# CON1.net
KiCad netlist of a schematic drawn in Altium Designer
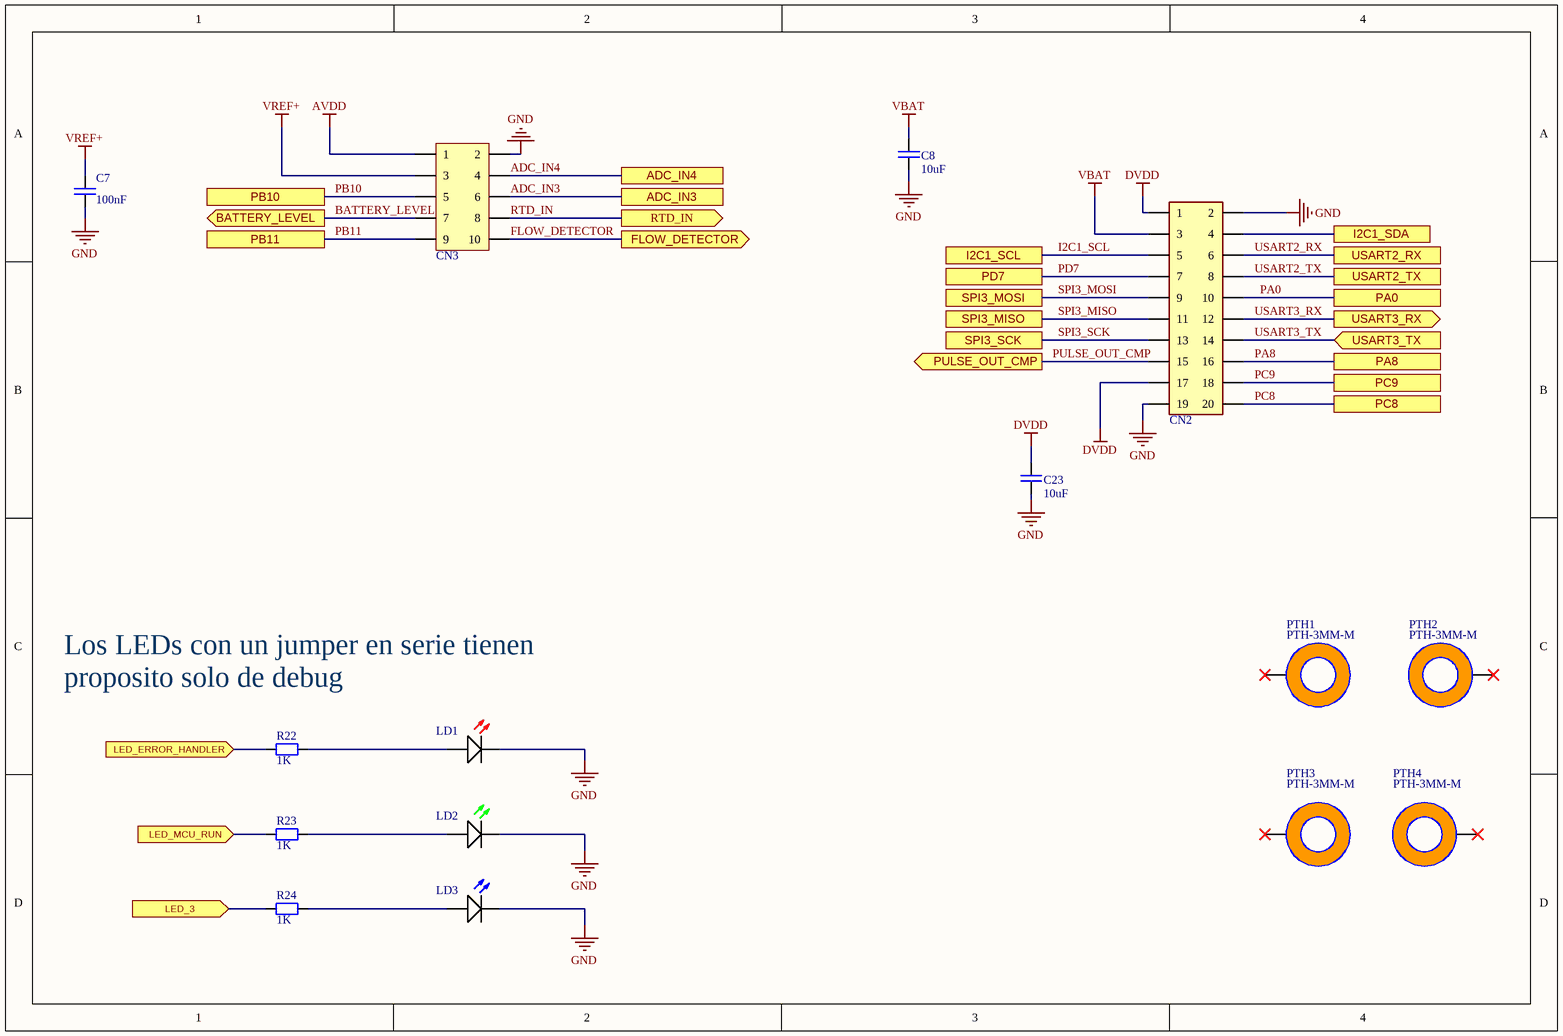
[diagram p0: CON1.SchDoc]

(export (version "E")
  (design (tool "Eeschema 10.0.6"))
  (components
    (comp (ref "C7")
      (value "100nF")
      (footprint "CAP_SM0805_YAGEOCC2_N")
      (description "CAP 100nF SM0805 X7R 50V YAGEO CC2")
      (fields
        (field (name "MANUFACTURER") "Yageo")
        (field (name "MANUFACTURER PART NUMBER") "CC0805KRX7R9BB104")
      )
      (libsource (lib "Yageo") (part "CC0805KRX7R9BB104"))
    )
    (comp (ref "C8")
      (value "10uF")
      (footprint "CAP_SM0805_YAGEOCC2_N")
      (description "CAP 10uF SM0805 X5R 25V YAGEO")
      (fields
        (field (name "MANUFACTURER") "Yageo")
        (field (name "MANUFACTURER PART NUMBER") "CC0805KKX5R8BB106")
      )
      (libsource (lib "Yageo") (part "CC0805KKX5R8BB106"))
    )
    (comp (ref "C23")
      (value "10uF")
      (footprint "CAP_SM0805_YAGEOCC2_N")
      (description "CAP 10uF SM0805 X5R 25V YAGEO")
      (fields
        (field (name "MANUFACTURER") "Yageo")
        (field (name "MANUFACTURER PART NUMBER") "CC0805KKX5R8BB106")
      )
      (libsource (lib "Yageo") (part "CC0805KKX5R8BB106"))
    )
    (comp (ref "CN2")
      (value "DW254R-22-20-85")
      (footprint "DW254R-22-10-85")
      (description "2 x 10 - true hole 2.54mm - altura 8.5mm")
      (fields (field (name "MANUFACTURER") "Dealon"))
      (libsource (lib "header_female") (part "DW254R-22-20-85"))
    )
    (comp (ref "CN3")
      (value "DW254S-22-10-85")
      (footprint "2X5 100 MILS SMD")
      (description "2 x 5 - SMD 2.54mm - altura 8.5mm")
      (fields (field (name "MANUFACTURER") "Dealon"))
      (libsource (lib "header_female") (part "DW254S-22-10-85"))
    )
    (comp (ref "LD1")
      (value "RED")
      (footprint "LED 0805")
      (fields
        (field (name "MANUFACTURER") "Everlight Elec")
        (field (name "MANUFACTURER PART NUMBER") "17-21SYGC/S530-E2/TR8")
      )
      (libsource (lib "LED") (part "17-21SYGC/S530-E2/TR8"))
    )
    (comp (ref "LD2")
      (value "GREEN")
      (footprint "LED 0805")
      (fields
        (field (name "MANUFACTURER") "Everlight Elec")
        (field (name "MANUFACTURER PART NUMBER") "17-21SYGC/S530-E2/TR8")
      )
      (libsource (lib "LED") (part "17-21SURC/S530-A2/TR8"))
    )
    (comp (ref "LD3")
      (value "BLUE")
      (footprint "LED 0805")
      (fields
        (field (name "MANUFACTURER") "Everlight Elec")
        (field (name "MANUFACTURER PART NUMBER") "17-21/BHC-XL2M2TY/3T")
      )
      (libsource (lib "LED") (part "17-21/BHC-XL2M2TY/3T"))
    )
    (comp (ref "PTH1")
      (value "PTH-3MM-M")
      (footprint "PTH_M3_M")
      (description "Agujero de montaje metalizado roscas M3. Drill de tamaño medio.")
      (libsource (lib "montaje") (part "PTH-3MM-M"))
    )
    (comp (ref "PTH2")
      (value "PTH-3MM-M")
      (footprint "PTH_M3_M")
      (description "Agujero de montaje metalizado roscas M3. Drill de tamaño medio.")
      (libsource (lib "montaje") (part "PTH-3MM-M"))
    )
    (comp (ref "PTH3")
      (value "PTH-3MM-M")
      (footprint "PTH_M3_M")
      (description "Agujero de montaje metalizado roscas M3. Drill de tamaño medio.")
      (libsource (lib "montaje") (part "PTH-3MM-M"))
    )
    (comp (ref "PTH4")
      (value "PTH-3MM-M")
      (footprint "PTH_M3_M")
      (description "Agujero de montaje metalizado roscas M3. Drill de tamaño medio.")
      (libsource (lib "montaje") (part "PTH-3MM-M"))
    )
    (comp (ref "R22")
      (value "1K")
      (footprint "RES_SM0805_YAGEORC_N")
      (description "RES 1K SM0805 YAGEO RC_L")
      (fields
        (field (name "MANUFACTURER") "Yageo")
        (field (name "MANUFACTURER PART NUMBER") "RC0805FR-071KL")
      )
      (libsource (lib "Yageo") (part "RC0805FR-071KL"))
    )
    (comp (ref "R23")
      (value "1K")
      (footprint "RES_SM0805_YAGEORC_N")
      (description "RES 1K SM0805 YAGEO RC_L")
      (fields
        (field (name "MANUFACTURER") "Yageo")
        (field (name "MANUFACTURER PART NUMBER") "RC0805FR-071KL")
      )
      (libsource (lib "Yageo") (part "RC0805FR-071KL"))
    )
    (comp (ref "R24")
      (value "1K")
      (footprint "RES_SM0805_YAGEORC_N")
      (description "RES 1K SM0805 YAGEO RC_L")
      (fields
        (field (name "MANUFACTURER") "Yageo")
        (field (name "MANUFACTURER PART NUMBER") "RC0805FR-071KL")
      )
      (libsource (lib "Yageo") (part "RC0805FR-071KL"))
    )
  )
  (nets
    (net (code "1") (name "/ADC_IN3") (class "Default")
      (node (ref "CN3") (pin "6") (pinfunction "6_6") (pintype "passive"))
    )
    (net (code "2") (name "/ADC_IN4") (class "Default")
      (node (ref "CN3") (pin "4") (pinfunction "4_4") (pintype "passive"))
    )
    (net (code "3") (name "/BATTERY_LEVEL") (class "Default")
      (node (ref "CN3") (pin "7") (pinfunction "7_7") (pintype "passive"))
    )
    (net (code "4") (name "/FLOW_DETECTOR") (class "Default")
      (node (ref "CN3") (pin "10") (pinfunction "10_10") (pintype "passive"))
    )
    (net (code "5") (name "/I2C1_SCL") (class "Default")
      (node (ref "CN2") (pin "5") (pinfunction "5_5") (pintype "passive"))
    )
    (net (code "6") (name "/I2C1_SDA") (class "Default")
      (node (ref "CN2") (pin "4") (pinfunction "4_4") (pintype "passive"))
    )
    (net (code "7") (name "/LED_3") (class "Default") (node (ref "R24") (pin "1") (pintype "passive")))
    (net (code "8") (name "/LED_ERROR_HANDLER") (class "Default")
      (node (ref "R22") (pin "1") (pintype "passive"))
    )
    (net (code "9") (name "/LED_MCU_RUN") (class "Default") (node (ref "R23") (pin "1") (pintype "passive")))
    (net (code "10") (name "/PA0") (class "Default")
      (node (ref "CN2") (pin "10") (pinfunction "10_10") (pintype "passive"))
    )
    (net (code "11") (name "/PA8") (class "Default")
      (node (ref "CN2") (pin "16") (pinfunction "16_16") (pintype "passive"))
    )
    (net (code "12") (name "/PB10") (class "Default")
      (node (ref "CN3") (pin "5") (pinfunction "5_5") (pintype "passive"))
    )
    (net (code "13") (name "/PB11") (class "Default")
      (node (ref "CN3") (pin "9") (pinfunction "9_9") (pintype "passive"))
    )
    (net (code "14") (name "/PC8") (class "Default")
      (node (ref "CN2") (pin "20") (pinfunction "20_20") (pintype "passive"))
    )
    (net (code "15") (name "/PC9") (class "Default")
      (node (ref "CN2") (pin "18") (pinfunction "18_18") (pintype "passive"))
    )
    (net (code "16") (name "/PD7") (class "Default")
      (node (ref "CN2") (pin "7") (pinfunction "7_7") (pintype "passive"))
    )
    (net (code "17") (name "/PULSE_OUT_CMP") (class "Default")
      (node (ref "CN2") (pin "15") (pinfunction "15_15") (pintype "passive"))
    )
    (net (code "18") (name "/RTD_IN") (class "Default")
      (node (ref "CN3") (pin "8") (pinfunction "8_8") (pintype "passive"))
    )
    (net (code "19") (name "/SPI3_MISO") (class "Default")
      (node (ref "CN2") (pin "11") (pinfunction "11_11") (pintype "passive"))
    )
    (net (code "20") (name "/SPI3_MOSI") (class "Default")
      (node (ref "CN2") (pin "9") (pinfunction "9_9") (pintype "passive"))
    )
    (net (code "21") (name "/SPI3_SCK") (class "Default")
      (node (ref "CN2") (pin "13") (pinfunction "13_13") (pintype "passive"))
    )
    (net (code "22") (name "/USART2_RX") (class "Default")
      (node (ref "CN2") (pin "6") (pinfunction "6_6") (pintype "passive"))
    )
    (net (code "23") (name "/USART2_TX") (class "Default")
      (node (ref "CN2") (pin "8") (pinfunction "8_8") (pintype "passive"))
    )
    (net (code "24") (name "/USART3_RX") (class "Default")
      (node (ref "CN2") (pin "12") (pinfunction "12_12") (pintype "passive"))
    )
    (net (code "25") (name "/USART3_TX") (class "Default")
      (node (ref "CN2") (pin "14") (pinfunction "14_14") (pintype "passive"))
    )
    (net (code "26") (name "AVDD") (class "Default")
      (node (ref "CN3") (pin "1") (pinfunction "1_1") (pintype "passive"))
    )
    (net (code "27") (name "DVDD") (class "Default")
      (node (ref "C23") (pin "2") (pintype "passive"))
      (node (ref "CN2") (pin "1") (pinfunction "1_1") (pintype "passive"))
      (node (ref "CN2") (pin "17") (pinfunction "17_17") (pintype "passive"))
    )
    (net (code "28") (name "GND") (class "Default")
      (node (ref "C23") (pin "1") (pintype "passive"))
      (node (ref "C7") (pin "2") (pintype "passive"))
      (node (ref "C8") (pin "2") (pintype "passive"))
      (node (ref "CN2") (pin "19") (pinfunction "19_19") (pintype "passive"))
      (node (ref "CN2") (pin "2") (pinfunction "2_2") (pintype "passive"))
      (node (ref "CN3") (pin "2") (pinfunction "2_2") (pintype "passive"))
      (node (ref "LD1") (pin "K") (pinfunction "K_K") (pintype "passive"))
      (node (ref "LD2") (pin "K") (pinfunction "K_K") (pintype "passive"))
      (node (ref "LD3") (pin "K") (pinfunction "K_K") (pintype "passive"))
    )
    (net (code "29") (name "Net-(LD1-PadA)") (class "Default")
      (node (ref "LD1") (pin "A") (pinfunction "A_A") (pintype "passive"))
      (node (ref "R22") (pin "2") (pintype "passive"))
    )
    (net (code "30") (name "Net-(LD2-PadA)") (class "Default")
      (node (ref "LD2") (pin "A") (pinfunction "A_A") (pintype "passive"))
      (node (ref "R23") (pin "2") (pintype "passive"))
    )
    (net (code "31") (name "Net-(LD3-PadA)") (class "Default")
      (node (ref "LD3") (pin "A") (pinfunction "A_A") (pintype "passive"))
      (node (ref "R24") (pin "2") (pintype "passive"))
    )
    (net (code "32") (name "VBAT") (class "Default")
      (node (ref "C8") (pin "1") (pintype "passive"))
      (node (ref "CN2") (pin "3") (pinfunction "3_3") (pintype "passive"))
    )
    (net (code "33") (name "VREF+") (class "Default")
      (node (ref "C7") (pin "1") (pintype "passive"))
      (node (ref "CN3") (pin "3") (pinfunction "3_3") (pintype "passive"))
    )
    (net (code "34") (name "unconnected-(PTH1-Pad1)") (class "Default")
      (node (ref "PTH1") (pin "1") (pinfunction "1_1") (pintype "passive+no_connect"))
    )
    (net (code "35") (name "unconnected-(PTH2-Pad1)") (class "Default")
      (node (ref "PTH2") (pin "1") (pinfunction "1_1") (pintype "passive+no_connect"))
    )
    (net (code "36") (name "unconnected-(PTH3-Pad1)") (class "Default")
      (node (ref "PTH3") (pin "1") (pinfunction "1_1") (pintype "passive+no_connect"))
    )
    (net (code "37") (name "unconnected-(PTH4-Pad1)") (class "Default")
      (node (ref "PTH4") (pin "1") (pinfunction "1_1") (pintype "passive+no_connect"))
    )
  )
)
